# smart_well.net
KiCad netlist of a schematic drawn in EAGLE
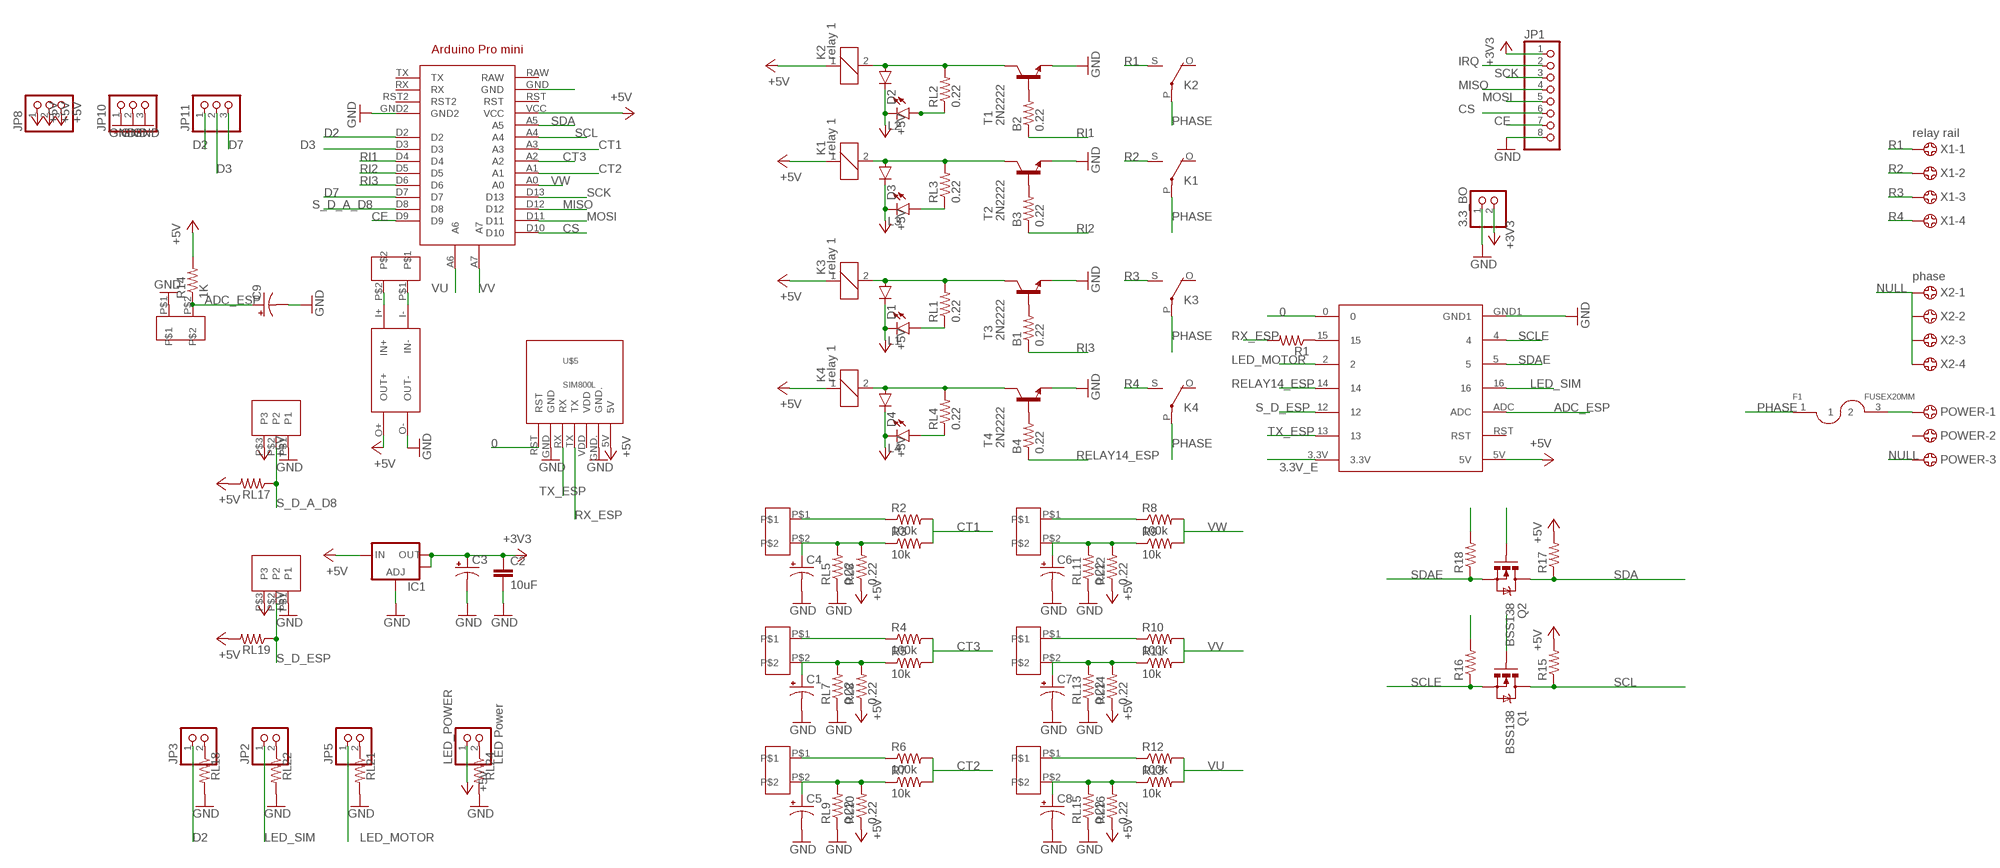
[diagram p0: schematic, sheet 1]

(export (version "E")
  (design (tool "Eeschema 10.0.6"))
  (components
    (comp (ref "3.3_BO")
      (value "PINHD-1X2")
      (footprint "eagle-import:1X02")
      (libsource (lib "eagle-import") (part "PINHD-1X2"))
    )
    (comp (ref "B1")
      (value "0.22")
      (footprint "eagle-import:0805")
      (libsource (lib "eagle-import") (part "0.22OHM-1/4W-1%(0805)"))
    )
    (comp (ref "B2")
      (value "0.22")
      (footprint "eagle-import:0805")
      (libsource (lib "eagle-import") (part "0.22OHM-1/4W-1%(0805)"))
    )
    (comp (ref "B3")
      (value "0.22")
      (footprint "eagle-import:0805")
      (libsource (lib "eagle-import") (part "0.22OHM-1/4W-1%(0805)"))
    )
    (comp (ref "B4")
      (value "0.22")
      (footprint "eagle-import:0805")
      (libsource (lib "eagle-import") (part "0.22OHM-1/4W-1%(0805)"))
    )
    (comp (ref "C1")
      (value "100UF-25V-20%(PTH)")
      (footprint "eagle-import:CPOL-RADIAL-100UF-25V")
      (libsource (lib "eagle-import") (part "100UF-25V-20%(PTH)"))
    )
    (comp (ref "C2")
      (value "10uF")
      (footprint "eagle-import:1210")
      (libsource (lib "eagle-import") (part "10UF50V20%(1210)"))
    )
    (comp (ref "C3")
      (value "100UF-25V-20%(PTH)")
      (footprint "eagle-import:CPOL-RADIAL-100UF-25V")
      (libsource (lib "eagle-import") (part "100UF-25V-20%(PTH)"))
    )
    (comp (ref "C4")
      (value "100UF-25V-20%(PTH)")
      (footprint "eagle-import:CPOL-RADIAL-100UF-25V")
      (libsource (lib "eagle-import") (part "100UF-25V-20%(PTH)"))
    )
    (comp (ref "C5")
      (value "100UF-25V-20%(PTH)")
      (footprint "eagle-import:CPOL-RADIAL-100UF-25V")
      (libsource (lib "eagle-import") (part "100UF-25V-20%(PTH)"))
    )
    (comp (ref "C6")
      (value "100UF-25V-20%(PTH)")
      (footprint "eagle-import:CPOL-RADIAL-100UF-25V")
      (libsource (lib "eagle-import") (part "100UF-25V-20%(PTH)"))
    )
    (comp (ref "C7")
      (value "100UF-25V-20%(PTH)")
      (footprint "eagle-import:CPOL-RADIAL-100UF-25V")
      (libsource (lib "eagle-import") (part "100UF-25V-20%(PTH)"))
    )
    (comp (ref "C8")
      (value "100UF-25V-20%(PTH)")
      (footprint "eagle-import:CPOL-RADIAL-100UF-25V")
      (libsource (lib "eagle-import") (part "100UF-25V-20%(PTH)"))
    )
    (comp (ref "C9")
      (value "10UF-25V-20%(PTH)KIT")
      (footprint "eagle-import:CPOL-RADIAL-10UF-25V-KIT")
      (libsource (lib "eagle-import") (part "10UF-25V-20%(PTH)KIT"))
    )
    (comp (ref "CT1")
      (value "ct1")
      (footprint "eagle-import:PIN_LOCK1X2")
      (libsource (lib "eagle-import") (part "PIN_LOCK_1X2"))
    )
    (comp (ref "CT2")
      (value "ct1")
      (footprint "eagle-import:PIN_LOCK1X2")
      (libsource (lib "eagle-import") (part "PIN_LOCK_1X2"))
    )
    (comp (ref "CT3")
      (value "ct1")
      (footprint "eagle-import:PIN_LOCK1X2")
      (libsource (lib "eagle-import") (part "PIN_LOCK_1X2"))
    )
    (comp (ref "CT4")
      (value "ct1")
      (footprint "eagle-import:PIN_LOCK1X2")
      (libsource (lib "eagle-import") (part "PIN_LOCK_1X2"))
    )
    (comp (ref "CT5")
      (value "ct1")
      (footprint "eagle-import:PIN_LOCK1X2")
      (libsource (lib "eagle-import") (part "PIN_LOCK_1X2"))
    )
    (comp (ref "CT6")
      (value "ct1")
      (footprint "eagle-import:PIN_LOCK1X2")
      (libsource (lib "eagle-import") (part "PIN_LOCK_1X2"))
    )
    (comp (ref "D1")
      (value "DIODEKIT2")
      (footprint "eagle-import:DIODE-1N4001-KIT")
      (libsource (lib "eagle-import") (part "DIODEKIT2"))
    )
    (comp (ref "D2")
      (value "DIODEKIT2")
      (footprint "eagle-import:DIODE-1N4001-KIT")
      (libsource (lib "eagle-import") (part "DIODEKIT2"))
    )
    (comp (ref "D3")
      (value "DIODEKIT2")
      (footprint "eagle-import:DIODE-1N4001-KIT")
      (libsource (lib "eagle-import") (part "DIODEKIT2"))
    )
    (comp (ref "D4")
      (value "DIODEKIT2")
      (footprint "eagle-import:DIODE-1N4001-KIT")
      (libsource (lib "eagle-import") (part "DIODEKIT2"))
    )
    (comp (ref "F1")
      (value "FUSEX20MM")
      (footprint "eagle-import:FUSE_5MM")
      (libsource (lib "eagle-import") (part "FUSEX20MM"))
    )
    (comp (ref "IC1")
      (value "V_REG_LM1117SOT223")
      (footprint "eagle-import:SOT223")
      (libsource (lib "eagle-import") (part "V_REG_LM1117SOT223"))
    )
    (comp (ref "JP1")
      (value "PINHD-1X8")
      (footprint "eagle-import:1X08")
      (libsource (lib "eagle-import") (part "PINHD-1X8"))
    )
    (comp (ref "JP2")
      (value "PINHD-1X2")
      (footprint "eagle-import:1X02")
      (libsource (lib "eagle-import") (part "PINHD-1X2"))
    )
    (comp (ref "JP3")
      (value "PINHD-1X2")
      (footprint "eagle-import:1X02")
      (libsource (lib "eagle-import") (part "PINHD-1X2"))
    )
    (comp (ref "JP5")
      (value "PINHD-1X2")
      (footprint "eagle-import:1X02")
      (libsource (lib "eagle-import") (part "PINHD-1X2"))
    )
    (comp (ref "JP8")
      (value "PINHD-1X3")
      (footprint "eagle-import:1X03")
      (libsource (lib "eagle-import") (part "PINHD-1X3"))
    )
    (comp (ref "JP10")
      (value "PINHD-1X3")
      (footprint "eagle-import:1X03")
      (libsource (lib "eagle-import") (part "PINHD-1X3"))
    )
    (comp (ref "JP11")
      (value "PINHD-1X3")
      (footprint "eagle-import:1X03")
      (libsource (lib "eagle-import") (part "PINHD-1X3"))
    )
    (comp (ref "K1")
      (value "relay 1")
      (footprint "eagle-import:G5LE")
      (libsource (lib "eagle-import") (part "G5LE"))
    )
    (comp (ref "K2")
      (value "relay 1")
      (footprint "eagle-import:G5LE")
      (libsource (lib "eagle-import") (part "G5LE"))
    )
    (comp (ref "K3")
      (value "relay 1")
      (footprint "eagle-import:G5LE")
      (libsource (lib "eagle-import") (part "G5LE"))
    )
    (comp (ref "K4")
      (value "relay 1")
      (footprint "eagle-import:G5LE")
      (libsource (lib "eagle-import") (part "G5LE"))
    )
    (comp (ref "L1")
      (value "LED3MM")
      (footprint "eagle-import:LED3MM")
      (libsource (lib "eagle-import") (part "LED3MM"))
    )
    (comp (ref "L2")
      (value "LED3MM")
      (footprint "eagle-import:LED3MM")
      (libsource (lib "eagle-import") (part "LED3MM"))
    )
    (comp (ref "L3")
      (value "LED3MM")
      (footprint "eagle-import:LED3MM")
      (libsource (lib "eagle-import") (part "LED3MM"))
    )
    (comp (ref "L4")
      (value "LED3MM")
      (footprint "eagle-import:LED3MM")
      (libsource (lib "eagle-import") (part "LED3MM"))
    )
    (comp (ref "LED_POWER")
      (value "LED Power")
      (footprint "eagle-import:1X02")
      (libsource (lib "eagle-import") (part "PINHD-1X2"))
    )
    (comp (ref "POWER")
      (value "5202-03-N-02")
      (footprint "eagle-import:5202-03-N-02")
      (libsource (lib "eagle-import") (part "5202-03-N-02"))
    )
    (comp (ref "Q1")
      (value "BSS138")
      (footprint "eagle-import:SOT23-3")
      (libsource (lib "eagle-import") (part "MOSFET-NCHANNELBSS138"))
    )
    (comp (ref "Q2")
      (value "BSS138")
      (footprint "eagle-import:SOT23-3")
      (libsource (lib "eagle-import") (part "MOSFET-NCHANNELBSS138"))
    )
    (comp (ref "R1")
      (value "0.3OHM-1/8W-1%(0805)")
      (footprint "eagle-import:0805")
      (libsource (lib "eagle-import") (part "0.3OHM-1/8W-1%(0805)"))
    )
    (comp (ref "R2")
      (value "100k")
      (footprint "eagle-import:AXIAL-0.1")
      (libsource (lib "eagle-import") (part "10OHM-1/4W-5%(PTH)VERT"))
    )
    (comp (ref "R3")
      (value "10k")
      (footprint "eagle-import:AXIAL-0.1")
      (libsource (lib "eagle-import") (part "10OHM-1/4W-5%(PTH)VERT"))
    )
    (comp (ref "R4")
      (value "100k")
      (footprint "eagle-import:AXIAL-0.1")
      (libsource (lib "eagle-import") (part "10OHM-1/4W-5%(PTH)VERT"))
    )
    (comp (ref "R5")
      (value "10k")
      (footprint "eagle-import:AXIAL-0.1")
      (libsource (lib "eagle-import") (part "10OHM-1/4W-5%(PTH)VERT"))
    )
    (comp (ref "R6")
      (value "100k")
      (footprint "eagle-import:AXIAL-0.1")
      (libsource (lib "eagle-import") (part "10OHM-1/4W-5%(PTH)VERT"))
    )
    (comp (ref "R7")
      (value "10k")
      (footprint "eagle-import:AXIAL-0.1")
      (libsource (lib "eagle-import") (part "10OHM-1/4W-5%(PTH)VERT"))
    )
    (comp (ref "R8")
      (value "100k")
      (footprint "eagle-import:AXIAL-0.1")
      (libsource (lib "eagle-import") (part "10OHM-1/4W-5%(PTH)VERT"))
    )
    (comp (ref "R9")
      (value "10k")
      (footprint "eagle-import:AXIAL-0.1")
      (libsource (lib "eagle-import") (part "10OHM-1/4W-5%(PTH)VERT"))
    )
    (comp (ref "R10")
      (value "100k")
      (footprint "eagle-import:AXIAL-0.1")
      (libsource (lib "eagle-import") (part "10OHM-1/4W-5%(PTH)VERT"))
    )
    (comp (ref "R11")
      (value "10k")
      (footprint "eagle-import:AXIAL-0.1")
      (libsource (lib "eagle-import") (part "10OHM-1/4W-5%(PTH)VERT"))
    )
    (comp (ref "R12")
      (value "100k")
      (footprint "eagle-import:AXIAL-0.1")
      (libsource (lib "eagle-import") (part "10OHM-1/4W-5%(PTH)VERT"))
    )
    (comp (ref "R13")
      (value "10k")
      (footprint "eagle-import:AXIAL-0.1")
      (libsource (lib "eagle-import") (part "10OHM-1/4W-5%(PTH)VERT"))
    )
    (comp (ref "R14")
      (value "1K")
      (footprint "eagle-import:AXIAL-0.1")
      (libsource (lib "eagle-import") (part "1KOHM-1/4W-1%(PTH)VERT"))
    )
    (comp (ref "R15")
      (value "0.22OHM-1/4W-1%(0805)")
      (footprint "eagle-import:0805")
      (libsource (lib "eagle-import") (part "0.22OHM-1/4W-1%(0805)"))
    )
    (comp (ref "R16")
      (value "0.22OHM-1/4W-1%(0805)")
      (footprint "eagle-import:0805")
      (libsource (lib "eagle-import") (part "0.22OHM-1/4W-1%(0805)"))
    )
    (comp (ref "R17")
      (value "0.22OHM-1/4W-1%(0805)")
      (footprint "eagle-import:0805")
      (libsource (lib "eagle-import") (part "0.22OHM-1/4W-1%(0805)"))
    )
    (comp (ref "R18")
      (value "0.22OHM-1/4W-1%(0805)")
      (footprint "eagle-import:0805")
      (libsource (lib "eagle-import") (part "0.22OHM-1/4W-1%(0805)"))
    )
    (comp (ref "RL1")
      (value "0.22")
      (footprint "eagle-import:0805")
      (libsource (lib "eagle-import") (part "0.22OHM-1/4W-1%(0805)"))
    )
    (comp (ref "RL2")
      (value "0.22")
      (footprint "eagle-import:0805")
      (libsource (lib "eagle-import") (part "0.22OHM-1/4W-1%(0805)"))
    )
    (comp (ref "RL3")
      (value "0.22")
      (footprint "eagle-import:0805")
      (libsource (lib "eagle-import") (part "0.22OHM-1/4W-1%(0805)"))
    )
    (comp (ref "RL4")
      (value "0.22")
      (footprint "eagle-import:0805")
      (libsource (lib "eagle-import") (part "0.22OHM-1/4W-1%(0805)"))
    )
    (comp (ref "RL5")
      (value "0.22")
      (footprint "eagle-import:0805")
      (libsource (lib "eagle-import") (part "0.22OHM-1/4W-1%(0805)"))
    )
    (comp (ref "RL6")
      (value "0.22")
      (footprint "eagle-import:0805")
      (libsource (lib "eagle-import") (part "0.22OHM-1/4W-1%(0805)"))
    )
    (comp (ref "RL7")
      (value "0.22")
      (footprint "eagle-import:0805")
      (libsource (lib "eagle-import") (part "0.22OHM-1/4W-1%(0805)"))
    )
    (comp (ref "RL8")
      (value "0.22")
      (footprint "eagle-import:0805")
      (libsource (lib "eagle-import") (part "0.22OHM-1/4W-1%(0805)"))
    )
    (comp (ref "RL9")
      (value "0.22")
      (footprint "eagle-import:0805")
      (libsource (lib "eagle-import") (part "0.22OHM-1/4W-1%(0805)"))
    )
    (comp (ref "RL10")
      (value "0.22")
      (footprint "eagle-import:0805")
      (libsource (lib "eagle-import") (part "0.22OHM-1/4W-1%(0805)"))
    )
    (comp (ref "RL11")
      (value "0.22")
      (footprint "eagle-import:0805")
      (libsource (lib "eagle-import") (part "0.22OHM-1/4W-1%(0805)"))
    )
    (comp (ref "RL12")
      (value "0.22")
      (footprint "eagle-import:0805")
      (libsource (lib "eagle-import") (part "0.22OHM-1/4W-1%(0805)"))
    )
    (comp (ref "RL13")
      (value "0.22")
      (footprint "eagle-import:0805")
      (libsource (lib "eagle-import") (part "0.22OHM-1/4W-1%(0805)"))
    )
    (comp (ref "RL14")
      (value "0.22")
      (footprint "eagle-import:0805")
      (libsource (lib "eagle-import") (part "0.22OHM-1/4W-1%(0805)"))
    )
    (comp (ref "RL15")
      (value "0.22")
      (footprint "eagle-import:0805")
      (libsource (lib "eagle-import") (part "0.22OHM-1/4W-1%(0805)"))
    )
    (comp (ref "RL16")
      (value "0.22")
      (footprint "eagle-import:0805")
      (libsource (lib "eagle-import") (part "0.22OHM-1/4W-1%(0805)"))
    )
    (comp (ref "RL17")
      (value "0.22OHM-1/4W-1%(0805)")
      (footprint "eagle-import:0805")
      (libsource (lib "eagle-import") (part "0.22OHM-1/4W-1%(0805)"))
    )
    (comp (ref "RL18")
      (value "0.22OHM-1/4W-1%(0805)")
      (footprint "eagle-import:0805")
      (libsource (lib "eagle-import") (part "0.22OHM-1/4W-1%(0805)"))
    )
    (comp (ref "RL19")
      (value "0.22OHM-1/4W-1%(0805)")
      (footprint "eagle-import:0805")
      (libsource (lib "eagle-import") (part "0.22OHM-1/4W-1%(0805)"))
    )
    (comp (ref "RL21")
      (value "0.22OHM-1/4W-1%(0805)")
      (footprint "eagle-import:0805")
      (libsource (lib "eagle-import") (part "0.22OHM-1/4W-1%(0805)"))
    )
    (comp (ref "RL22")
      (value "0.22OHM-1/4W-1%(0805)")
      (footprint "eagle-import:0805")
      (libsource (lib "eagle-import") (part "0.22OHM-1/4W-1%(0805)"))
    )
    (comp (ref "RL24")
      (value "0.22OHM-1/4W-1%(0805)")
      (footprint "eagle-import:0805")
      (libsource (lib "eagle-import") (part "0.22OHM-1/4W-1%(0805)"))
    )
    (comp (ref "T1")
      (value "2N2222")
      (footprint "eagle-import:TO92-EBC-OVAL")
      (libsource (lib "eagle-import") (part "2N2222"))
    )
    (comp (ref "T2")
      (value "2N2222")
      (footprint "eagle-import:TO92-EBC-OVAL")
      (libsource (lib "eagle-import") (part "2N2222"))
    )
    (comp (ref "T3")
      (value "2N2222")
      (footprint "eagle-import:TO92-EBC-OVAL")
      (libsource (lib "eagle-import") (part "2N2222"))
    )
    (comp (ref "T4")
      (value "2N2222")
      (footprint "eagle-import:TO92-EBC-OVAL")
      (libsource (lib "eagle-import") (part "2N2222"))
    )
    (comp (ref "U$2")
      (value "PIN_LOCK_1X3")
      (footprint "eagle-import:PIN_LOCK1X3")
      (libsource (lib "eagle-import") (part "PIN_LOCK_1X3"))
    )
    (comp (ref "U$3")
      (value "ESP12F_SHEILD10PIN")
      (footprint "eagle-import:ESP12F_SHEILD10PIN")
      (libsource (lib "eagle-import") (part "ESP12F_SHEILD10PIN"))
    )
    (comp (ref "U$5")
      (value "SIM800L")
      (footprint "eagle-import:SIM800L")
      (libsource (lib "eagle-import") (part "SIM800L"))
    )
    (comp (ref "U$6")
      (value "DC-DC")
      (footprint "eagle-import:DC-DC")
      (libsource (lib "eagle-import") (part "DC-DC"))
    )
    (comp (ref "U$7")
      (value "ARDUINO_DIP")
      (footprint "eagle-import:ARDUINO_DIP")
      (libsource (lib "eagle-import") (part "ARDUINO_DIP"))
    )
    (comp (ref "U$8")
      (value "PIN_LOCK_1X3")
      (footprint "eagle-import:PIN_LOCK1X3")
      (libsource (lib "eagle-import") (part "PIN_LOCK_1X3"))
    )
    (comp (ref "U$9")
      (value "PIN_LOCK_1X2")
      (footprint "eagle-import:PIN_LOCK1X2")
      (libsource (lib "eagle-import") (part "PIN_LOCK_1X2"))
    )
    (comp (ref "U$11")
      (value "PIN_LOCK_1X2")
      (footprint "eagle-import:PIN_LOCK1X2")
      (libsource (lib "eagle-import") (part "PIN_LOCK_1X2"))
    )
    (comp (ref "X1")
      (value "relay rail")
      (footprint "eagle-import:5202-04-N-02")
      (libsource (lib "eagle-import") (part "5202-04-N-02"))
    )
    (comp (ref "X2")
      (value "phase")
      (footprint "eagle-import:5202-04-N-02")
      (libsource (lib "eagle-import") (part "5202-04-N-02"))
    )
  )
  (nets
    (net (code "1") (name "+3V3") (class "Default")
      (node (ref "3.3_BO") (pin "2") (pinfunction "2_2") (pintype "passive"))
      (node (ref "C2") (pin "1") (pinfunction "1_1") (pintype "passive"))
      (node (ref "C3") (pin "1") (pinfunction "+_1") (pintype "passive"))
      (node (ref "IC1") (pin "2") (pinfunction "OUT_2") (pintype "output"))
      (node (ref "IC1") (pin "4") (pinfunction "OUT_4") (pintype "output"))
      (node (ref "JP1") (pin "1") (pinfunction "1_1") (pintype "passive"))
    )
    (net (code "2") (name "+5V") (class "Default")
      (node (ref "D1") (pin "C") (pinfunction "C_C") (pintype "passive"))
      (node (ref "D2") (pin "C") (pinfunction "C_C") (pintype "passive"))
      (node (ref "D3") (pin "C") (pinfunction "C_C") (pintype "passive"))
      (node (ref "D4") (pin "C") (pinfunction "C_C") (pintype "passive"))
      (node (ref "IC1") (pin "3") (pinfunction "IN_3") (pintype "input"))
      (node (ref "JP8") (pin "1") (pinfunction "1_1") (pintype "passive"))
      (node (ref "JP8") (pin "2") (pinfunction "2_2") (pintype "passive"))
      (node (ref "JP8") (pin "3") (pinfunction "3_3") (pintype "passive"))
      (node (ref "K1") (pin "1") (pinfunction "1_1") (pintype "passive"))
      (node (ref "K2") (pin "1") (pinfunction "1_1") (pintype "passive"))
      (node (ref "K3") (pin "1") (pinfunction "1_1") (pintype "passive"))
      (node (ref "K4") (pin "1") (pinfunction "1_1") (pintype "passive"))
      (node (ref "L1") (pin "K") (pinfunction "C_K") (pintype "passive"))
      (node (ref "L2") (pin "K") (pinfunction "C_K") (pintype "passive"))
      (node (ref "L3") (pin "K") (pinfunction "C_K") (pintype "passive"))
      (node (ref "L4") (pin "K") (pinfunction "C_K") (pintype "passive"))
      (node (ref "LED_POWER") (pin "1") (pinfunction "1_1") (pintype "passive"))
      (node (ref "R14") (pin "P$2") (pinfunction "2_P$2") (pintype "passive"))
      (node (ref "R15") (pin "2") (pinfunction "2_2") (pintype "passive"))
      (node (ref "R17") (pin "2") (pinfunction "2_2") (pintype "passive"))
      (node (ref "RL10") (pin "1") (pinfunction "1_1") (pintype "passive"))
      (node (ref "RL12") (pin "1") (pinfunction "1_1") (pintype "passive"))
      (node (ref "RL14") (pin "1") (pinfunction "1_1") (pintype "passive"))
      (node (ref "RL16") (pin "1") (pinfunction "1_1") (pintype "passive"))
      (node (ref "RL17") (pin "2") (pinfunction "2_2") (pintype "passive"))
      (node (ref "RL19") (pin "2") (pinfunction "2_2") (pintype "passive"))
      (node (ref "RL6") (pin "1") (pinfunction "1_1") (pintype "passive"))
      (node (ref "RL8") (pin "1") (pinfunction "1_1") (pintype "passive"))
      (node (ref "U$2") (pin "P$3") (pinfunction "P3_P$3") (pintype "bidirectional"))
      (node (ref "U$3") (pin "5V") (pinfunction "5V_5V") (pintype "bidirectional"))
      (node (ref "U$5") (pin "5V") (pinfunction "5V_5V") (pintype "bidirectional"))
      (node (ref "U$6") (pin "O+") (pinfunction "OUT+_O+") (pintype "bidirectional"))
      (node (ref "U$7") (pin "VCC") (pinfunction "VCC_VCC") (pintype "power_in"))
      (node (ref "U$8") (pin "P$3") (pinfunction "P3_P$3") (pintype "bidirectional"))
    )
    (net (code "3") (name "/0") (class "Default")
      (node (ref "U$3") (pin "0") (pinfunction "0_0") (pintype "bidirectional"))
      (node (ref "U$5") (pin "RST") (pinfunction "RST_RST") (pintype "bidirectional"))
    )
    (net (code "4") (name "/3.3V_E") (class "Default")
      (node (ref "Q1") (pin "1") (pinfunction "G_1") (pintype "passive"))
      (node (ref "Q2") (pin "1") (pinfunction "G_1") (pintype "passive"))
      (node (ref "R16") (pin "2") (pinfunction "2_2") (pintype "passive"))
      (node (ref "R18") (pin "2") (pinfunction "2_2") (pintype "passive"))
      (node (ref "U$3") (pin "3.3V") (pinfunction "3.3V_3.3V") (pintype "bidirectional"))
    )
    (net (code "5") (name "/ADC_ESP") (class "Default")
      (node (ref "C9") (pin "1") (pinfunction "+_1") (pintype "passive"))
      (node (ref "R14") (pin "P$1") (pinfunction "1_P$1") (pintype "passive"))
      (node (ref "U$11") (pin "P$2") (pinfunction "P$2_P$2") (pintype "bidirectional"))
      (node (ref "U$3") (pin "ADC") (pinfunction "ADC_ADC") (pintype "bidirectional"))
    )
    (net (code "6") (name "/CE") (class "Default")
      (node (ref "JP1") (pin "7") (pinfunction "7_7") (pintype "passive"))
      (node (ref "U$7") (pin "D9") (pinfunction "D9_D9") (pintype "bidirectional"))
    )
    (net (code "7") (name "/CS") (class "Default")
      (node (ref "JP1") (pin "6") (pinfunction "6_6") (pintype "passive"))
      (node (ref "U$7") (pin "D10") (pinfunction "D10_D10") (pintype "bidirectional"))
    )
    (net (code "8") (name "/CT1") (class "Default")
      (node (ref "R2") (pin "P$2") (pinfunction "2_P$2") (pintype "passive"))
      (node (ref "R3") (pin "P$2") (pinfunction "2_P$2") (pintype "passive"))
      (node (ref "U$7") (pin "A3") (pinfunction "A3_A3") (pintype "bidirectional"))
    )
    (net (code "9") (name "/CT2") (class "Default")
      (node (ref "R6") (pin "P$2") (pinfunction "2_P$2") (pintype "passive"))
      (node (ref "R7") (pin "P$2") (pinfunction "2_P$2") (pintype "passive"))
      (node (ref "U$7") (pin "A1") (pinfunction "A1_A1") (pintype "bidirectional"))
    )
    (net (code "10") (name "/CT3") (class "Default")
      (node (ref "R4") (pin "P$2") (pinfunction "2_P$2") (pintype "passive"))
      (node (ref "R5") (pin "P$2") (pinfunction "2_P$2") (pintype "passive"))
      (node (ref "U$7") (pin "A2") (pinfunction "A2_A2") (pintype "bidirectional"))
    )
    (net (code "11") (name "/D2") (class "Default")
      (node (ref "JP11") (pin "1") (pinfunction "1_1") (pintype "passive"))
      (node (ref "JP3") (pin "1") (pinfunction "1_1") (pintype "passive"))
      (node (ref "U$7") (pin "D2") (pinfunction "D2_D2") (pintype "bidirectional"))
    )
    (net (code "12") (name "/D3") (class "Default")
      (node (ref "JP11") (pin "2") (pinfunction "2_2") (pintype "passive"))
      (node (ref "U$7") (pin "D3") (pinfunction "D3_D3") (pintype "bidirectional"))
    )
    (net (code "13") (name "/D7") (class "Default")
      (node (ref "JP11") (pin "3") (pinfunction "3_3") (pintype "passive"))
      (node (ref "U$7") (pin "D7") (pinfunction "D7_D7") (pintype "bidirectional"))
    )
    (net (code "14") (name "/IRQ") (class "Default")
      (node (ref "JP1") (pin "2") (pinfunction "2_2") (pintype "passive"))
    )
    (net (code "15") (name "/LED_MOTOR") (class "Default")
      (node (ref "JP5") (pin "1") (pinfunction "1_1") (pintype "passive"))
      (node (ref "U$3") (pin "2") (pinfunction "2_2") (pintype "bidirectional"))
    )
    (net (code "16") (name "/LED_SIM") (class "Default")
      (node (ref "JP2") (pin "1") (pinfunction "1_1") (pintype "passive"))
      (node (ref "U$3") (pin "16") (pinfunction "16_16") (pintype "bidirectional"))
    )
    (net (code "17") (name "/MISO") (class "Default")
      (node (ref "JP1") (pin "4") (pinfunction "4_4") (pintype "passive"))
      (node (ref "U$7") (pin "D12") (pinfunction "D12_D12") (pintype "bidirectional"))
    )
    (net (code "18") (name "/MOSI") (class "Default")
      (node (ref "JP1") (pin "5") (pinfunction "5_5") (pintype "passive"))
      (node (ref "U$7") (pin "D11") (pinfunction "D11_D11") (pintype "bidirectional"))
    )
    (net (code "19") (name "/NULL") (class "Default")
      (node (ref "POWER") (pin "3") (pinfunction "1_3") (pintype "passive"))
      (node (ref "X2") (pin "1") (pinfunction "1_1") (pintype "passive"))
      (node (ref "X2") (pin "2") (pinfunction "1_2") (pintype "passive"))
      (node (ref "X2") (pin "3") (pinfunction "1_3") (pintype "passive"))
      (node (ref "X2") (pin "4") (pinfunction "1_4") (pintype "passive"))
    )
    (net (code "20") (name "/PHASE") (class "Default")
      (node (ref "F1") (pin "1") (pinfunction "1_1") (pintype "bidirectional"))
      (node (ref "K1") (pin "P") (pinfunction "P_P") (pintype "passive"))
      (node (ref "K2") (pin "P") (pinfunction "P_P") (pintype "passive"))
      (node (ref "K3") (pin "P") (pinfunction "P_P") (pintype "passive"))
      (node (ref "K4") (pin "P") (pinfunction "P_P") (pintype "passive"))
    )
    (net (code "21") (name "/R1") (class "Default")
      (node (ref "K2") (pin "S") (pinfunction "S_S") (pintype "passive"))
      (node (ref "X1") (pin "1") (pinfunction "1_1") (pintype "passive"))
    )
    (net (code "22") (name "/R2") (class "Default")
      (node (ref "K1") (pin "S") (pinfunction "S_S") (pintype "passive"))
      (node (ref "X1") (pin "2") (pinfunction "1_2") (pintype "passive"))
    )
    (net (code "23") (name "/R3") (class "Default")
      (node (ref "K3") (pin "S") (pinfunction "S_S") (pintype "passive"))
      (node (ref "X1") (pin "3") (pinfunction "1_3") (pintype "passive"))
    )
    (net (code "24") (name "/R4") (class "Default")
      (node (ref "K4") (pin "S") (pinfunction "S_S") (pintype "passive"))
      (node (ref "X1") (pin "4") (pinfunction "1_4") (pintype "passive"))
    )
    (net (code "25") (name "/RELAY14_ESP") (class "Default")
      (node (ref "B4") (pin "1") (pinfunction "1_1") (pintype "passive"))
      (node (ref "U$3") (pin "14") (pinfunction "14_14") (pintype "bidirectional"))
    )
    (net (code "26") (name "/RI1") (class "Default")
      (node (ref "B2") (pin "1") (pinfunction "1_1") (pintype "passive"))
      (node (ref "U$7") (pin "D4") (pinfunction "D4_D4") (pintype "bidirectional"))
    )
    (net (code "27") (name "/RI2") (class "Default")
      (node (ref "B3") (pin "1") (pinfunction "1_1") (pintype "passive"))
      (node (ref "U$7") (pin "D5") (pinfunction "D5_D5") (pintype "bidirectional"))
    )
    (net (code "28") (name "/RI3") (class "Default")
      (node (ref "B1") (pin "1") (pinfunction "1_1") (pintype "passive"))
      (node (ref "U$7") (pin "D6") (pinfunction "D6_D6") (pintype "bidirectional"))
    )
    (net (code "29") (name "/RX_ESP") (class "Default")
      (node (ref "R1") (pin "2") (pinfunction "2_2") (pintype "passive"))
      (node (ref "U$5") (pin "TX") (pinfunction "TX_TX") (pintype "bidirectional"))
    )
    (net (code "30") (name "/SCK") (class "Default")
      (node (ref "JP1") (pin "3") (pinfunction "3_3") (pintype "passive"))
      (node (ref "U$7") (pin "D13") (pinfunction "D13_D13") (pintype "bidirectional"))
    )
    (net (code "31") (name "/SCL") (class "Default")
      (node (ref "Q1") (pin "3") (pinfunction "D_3") (pintype "passive"))
      (node (ref "R15") (pin "1") (pinfunction "1_1") (pintype "passive"))
      (node (ref "U$7") (pin "A4") (pinfunction "A4_A4") (pintype "bidirectional"))
    )
    (net (code "32") (name "/SCLE") (class "Default")
      (node (ref "Q1") (pin "2") (pinfunction "S_2") (pintype "passive"))
      (node (ref "R16") (pin "1") (pinfunction "1_1") (pintype "passive"))
      (node (ref "U$3") (pin "4") (pinfunction "4_4") (pintype "bidirectional"))
    )
    (net (code "33") (name "/SDA") (class "Default")
      (node (ref "Q2") (pin "3") (pinfunction "D_3") (pintype "passive"))
      (node (ref "R17") (pin "1") (pinfunction "1_1") (pintype "passive"))
      (node (ref "U$7") (pin "A5") (pinfunction "A5_A5") (pintype "bidirectional"))
    )
    (net (code "34") (name "/SDAE") (class "Default")
      (node (ref "Q2") (pin "2") (pinfunction "S_2") (pintype "passive"))
      (node (ref "R18") (pin "1") (pinfunction "1_1") (pintype "passive"))
      (node (ref "U$3") (pin "5") (pinfunction "5_5") (pintype "bidirectional"))
    )
    (net (code "35") (name "/S_D_A_D8") (class "Default")
      (node (ref "RL17") (pin "1") (pinfunction "1_1") (pintype "passive"))
      (node (ref "U$2") (pin "P$2") (pinfunction "P2_P$2") (pintype "bidirectional"))
      (node (ref "U$7") (pin "D8") (pinfunction "D8_D8") (pintype "bidirectional"))
    )
    (net (code "36") (name "/S_D_ESP") (class "Default")
      (node (ref "RL19") (pin "1") (pinfunction "1_1") (pintype "passive"))
      (node (ref "U$3") (pin "12") (pinfunction "12_12") (pintype "bidirectional"))
      (node (ref "U$8") (pin "P$2") (pinfunction "P2_P$2") (pintype "bidirectional"))
    )
    (net (code "37") (name "/TX_ESP") (class "Default")
      (node (ref "U$3") (pin "13") (pinfunction "13_13") (pintype "bidirectional"))
      (node (ref "U$5") (pin "RX") (pinfunction "RX_RX") (pintype "bidirectional"))
    )
    (net (code "38") (name "/VU") (class "Default")
      (node (ref "R12") (pin "P$2") (pinfunction "2_P$2") (pintype "passive"))
      (node (ref "R13") (pin "P$2") (pinfunction "2_P$2") (pintype "passive"))
      (node (ref "U$7") (pin "A6") (pinfunction "A6_A6") (pintype "bidirectional"))
    )
    (net (code "39") (name "/VV") (class "Default")
      (node (ref "R10") (pin "P$2") (pinfunction "2_P$2") (pintype "passive"))
      (node (ref "R11") (pin "P$2") (pinfunction "2_P$2") (pintype "passive"))
      (node (ref "U$7") (pin "A7") (pinfunction "A7_A7") (pintype "bidirectional"))
    )
    (net (code "40") (name "/VW") (class "Default")
      (node (ref "R8") (pin "P$2") (pinfunction "2_P$2") (pintype "passive"))
      (node (ref "R9") (pin "P$2") (pinfunction "2_P$2") (pintype "passive"))
      (node (ref "U$7") (pin "A0") (pinfunction "A0_A0") (pintype "bidirectional"))
    )
    (net (code "41") (name "GND") (class "Default")
      (node (ref "3.3_BO") (pin "1") (pinfunction "1_1") (pintype "passive"))
      (node (ref "C1") (pin "2") (pinfunction "-_2") (pintype "passive"))
      (node (ref "C2") (pin "2") (pinfunction "2_2") (pintype "passive"))
      (node (ref "C3") (pin "2") (pinfunction "-_2") (pintype "passive"))
      (node (ref "C4") (pin "2") (pinfunction "-_2") (pintype "passive"))
      (node (ref "C5") (pin "2") (pinfunction "-_2") (pintype "passive"))
      (node (ref "C6") (pin "2") (pinfunction "-_2") (pintype "passive"))
      (node (ref "C7") (pin "2") (pinfunction "-_2") (pintype "passive"))
      (node (ref "C8") (pin "2") (pinfunction "-_2") (pintype "passive"))
      (node (ref "C9") (pin "2") (pinfunction "-_2") (pintype "passive"))
      (node (ref "IC1") (pin "1") (pinfunction "ADJ_1") (pintype "input"))
      (node (ref "JP1") (pin "8") (pinfunction "8_8") (pintype "passive"))
      (node (ref "JP10") (pin "1") (pinfunction "1_1") (pintype "passive"))
      (node (ref "JP10") (pin "2") (pinfunction "2_2") (pintype "passive"))
      (node (ref "JP10") (pin "3") (pinfunction "3_3") (pintype "passive"))
      (node (ref "RL11") (pin "1") (pinfunction "1_1") (pintype "passive"))
      (node (ref "RL13") (pin "1") (pinfunction "1_1") (pintype "passive"))
      (node (ref "RL15") (pin "1") (pinfunction "1_1") (pintype "passive"))
      (node (ref "RL18") (pin "2") (pinfunction "2_2") (pintype "passive"))
      (node (ref "RL21") (pin "2") (pinfunction "2_2") (pintype "passive"))
      (node (ref "RL22") (pin "2") (pinfunction "2_2") (pintype "passive"))
      (node (ref "RL24") (pin "2") (pinfunction "2_2") (pintype "passive"))
      (node (ref "RL5") (pin "1") (pinfunction "1_1") (pintype "passive"))
      (node (ref "RL7") (pin "1") (pinfunction "1_1") (pintype "passive"))
      (node (ref "RL9") (pin "1") (pinfunction "1_1") (pintype "passive"))
      (node (ref "T1") (pin "E") (pinfunction "E_E") (pintype "passive"))
      (node (ref "T2") (pin "E") (pinfunction "E_E") (pintype "passive"))
      (node (ref "T3") (pin "E") (pinfunction "E_E") (pintype "passive"))
      (node (ref "T4") (pin "E") (pinfunction "E_E") (pintype "passive"))
      (node (ref "U$11") (pin "P$1") (pinfunction "P$1_P$1") (pintype "bidirectional"))
      (node (ref "U$2") (pin "P$1") (pinfunction "P1_P$1") (pintype "bidirectional"))
      (node (ref "U$3") (pin "GND1") (pinfunction "GND1_GND1") (pintype "bidirectional"))
      (node (ref "U$5") (pin "GND") (pinfunction "GND_GND") (pintype "bidirectional"))
      (node (ref "U$5") (pin "GND.") (pinfunction "GND._GND.") (pintype "bidirectional"))
      (node (ref "U$6") (pin "O-") (pinfunction "OUT-_O-") (pintype "bidirectional"))
      (node (ref "U$7") (pin "GND2") (pinfunction "GND2_GND2") (pintype "bidirectional"))
      (node (ref "U$8") (pin "P$1") (pinfunction "P1_P$1") (pintype "bidirectional"))
    )
    (net (code "42") (name "Net-(B1-Pad2)") (class "Default")
      (node (ref "B1") (pin "2") (pinfunction "2_2") (pintype "passive"))
      (node (ref "T3") (pin "B") (pinfunction "B_B") (pintype "passive"))
    )
    (net (code "43") (name "Net-(B2-Pad2)") (class "Default")
      (node (ref "B2") (pin "2") (pinfunction "2_2") (pintype "passive"))
      (node (ref "T1") (pin "B") (pinfunction "B_B") (pintype "passive"))
    )
    (net (code "44") (name "Net-(B3-Pad2)") (class "Default")
      (node (ref "B3") (pin "2") (pinfunction "2_2") (pintype "passive"))
      (node (ref "T2") (pin "B") (pinfunction "B_B") (pintype "passive"))
    )
    (net (code "45") (name "Net-(B4-Pad2)") (class "Default")
      (node (ref "B4") (pin "2") (pinfunction "2_2") (pintype "passive"))
      (node (ref "T4") (pin "B") (pinfunction "B_B") (pintype "passive"))
    )
    (net (code "46") (name "Net-(C1-+)") (class "Default")
      (node (ref "C1") (pin "1") (pinfunction "+_1") (pintype "passive"))
      (node (ref "CT2") (pin "P$2") (pinfunction "P$2_P$2") (pintype "bidirectional"))
      (node (ref "R5") (pin "P$1") (pinfunction "1_P$1") (pintype "passive"))
      (node (ref "RL7") (pin "2") (pinfunction "2_2") (pintype "passive"))
      (node (ref "RL8") (pin "2") (pinfunction "2_2") (pintype "passive"))
    )
    (net (code "47") (name "Net-(C4-+)") (class "Default")
      (node (ref "C4") (pin "1") (pinfunction "+_1") (pintype "passive"))
      (node (ref "CT1") (pin "P$2") (pinfunction "P$2_P$2") (pintype "bidirectional"))
      (node (ref "R3") (pin "P$1") (pinfunction "1_P$1") (pintype "passive"))
      (node (ref "RL5") (pin "2") (pinfunction "2_2") (pintype "passive"))
      (node (ref "RL6") (pin "2") (pinfunction "2_2") (pintype "passive"))
    )
    (net (code "48") (name "Net-(C5-+)") (class "Default")
      (node (ref "C5") (pin "1") (pinfunction "+_1") (pintype "passive"))
      (node (ref "CT3") (pin "P$2") (pinfunction "P$2_P$2") (pintype "bidirectional"))
      (node (ref "R7") (pin "P$1") (pinfunction "1_P$1") (pintype "passive"))
      (node (ref "RL10") (pin "2") (pinfunction "2_2") (pintype "passive"))
      (node (ref "RL9") (pin "2") (pinfunction "2_2") (pintype "passive"))
    )
    (net (code "49") (name "Net-(C6-+)") (class "Default")
      (node (ref "C6") (pin "1") (pinfunction "+_1") (pintype "passive"))
      (node (ref "CT4") (pin "P$2") (pinfunction "P$2_P$2") (pintype "bidirectional"))
      (node (ref "R9") (pin "P$1") (pinfunction "1_P$1") (pintype "passive"))
      (node (ref "RL11") (pin "2") (pinfunction "2_2") (pintype "passive"))
      (node (ref "RL12") (pin "2") (pinfunction "2_2") (pintype "passive"))
    )
    (net (code "50") (name "Net-(C7-+)") (class "Default")
      (node (ref "C7") (pin "1") (pinfunction "+_1") (pintype "passive"))
      (node (ref "CT5") (pin "P$2") (pinfunction "P$2_P$2") (pintype "bidirectional"))
      (node (ref "R11") (pin "P$1") (pinfunction "1_P$1") (pintype "passive"))
      (node (ref "RL13") (pin "2") (pinfunction "2_2") (pintype "passive"))
      (node (ref "RL14") (pin "2") (pinfunction "2_2") (pintype "passive"))
    )
    (net (code "51") (name "Net-(C8-+)") (class "Default")
      (node (ref "C8") (pin "1") (pinfunction "+_1") (pintype "passive"))
      (node (ref "CT6") (pin "P$2") (pinfunction "P$2_P$2") (pintype "bidirectional"))
      (node (ref "R13") (pin "P$1") (pinfunction "1_P$1") (pintype "passive"))
      (node (ref "RL15") (pin "2") (pinfunction "2_2") (pintype "passive"))
      (node (ref "RL16") (pin "2") (pinfunction "2_2") (pintype "passive"))
    )
    (net (code "52") (name "Net-(D1-PadA)") (class "Default")
      (node (ref "D1") (pin "A") (pinfunction "A_A") (pintype "passive"))
      (node (ref "K3") (pin "2") (pinfunction "2_2") (pintype "passive"))
      (node (ref "RL1") (pin "2") (pinfunction "2_2") (pintype "passive"))
      (node (ref "T3") (pin "C") (pinfunction "C_C") (pintype "passive"))
    )
    (net (code "53") (name "Net-(D2-PadA)") (class "Default")
      (node (ref "D2") (pin "A") (pinfunction "A_A") (pintype "passive"))
      (node (ref "K2") (pin "2") (pinfunction "2_2") (pintype "passive"))
      (node (ref "RL2") (pin "2") (pinfunction "2_2") (pintype "passive"))
      (node (ref "T1") (pin "C") (pinfunction "C_C") (pintype "passive"))
    )
    (net (code "54") (name "Net-(D3-PadA)") (class "Default")
      (node (ref "D3") (pin "A") (pinfunction "A_A") (pintype "passive"))
      (node (ref "K1") (pin "2") (pinfunction "2_2") (pintype "passive"))
      (node (ref "RL3") (pin "2") (pinfunction "2_2") (pintype "passive"))
      (node (ref "T2") (pin "C") (pinfunction "C_C") (pintype "passive"))
    )
    (net (code "55") (name "Net-(D4-PadA)") (class "Default")
      (node (ref "D4") (pin "A") (pinfunction "A_A") (pintype "passive"))
      (node (ref "K4") (pin "2") (pinfunction "2_2") (pintype "passive"))
      (node (ref "RL4") (pin "2") (pinfunction "2_2") (pintype "passive"))
      (node (ref "T4") (pin "C") (pinfunction "C_C") (pintype "passive"))
    )
    (net (code "56") (name "Net-(F1-2)") (class "Default")
      (node (ref "F1") (pin "3") (pinfunction "2_3") (pintype "bidirectional"))
      (node (ref "POWER") (pin "1") (pinfunction "1_1") (pintype "passive"))
    )
    (net (code "57") (name "Net-(JP2-Pad2)") (class "Default")
      (node (ref "JP2") (pin "2") (pinfunction "2_2") (pintype "passive"))
      (node (ref "RL22") (pin "1") (pinfunction "1_1") (pintype "passive"))
    )
    (net (code "58") (name "Net-(JP3-Pad2)") (class "Default")
      (node (ref "JP3") (pin "2") (pinfunction "2_2") (pintype "passive"))
      (node (ref "RL18") (pin "1") (pinfunction "1_1") (pintype "passive"))
    )
    (net (code "59") (name "Net-(JP5-Pad2)") (class "Default")
      (node (ref "JP5") (pin "2") (pinfunction "2_2") (pintype "passive"))
      (node (ref "RL21") (pin "1") (pinfunction "1_1") (pintype "passive"))
    )
    (net (code "60") (name "Net-(L1-PadA)") (class "Default")
      (node (ref "L1") (pin "A") (pinfunction "A_A") (pintype "passive"))
      (node (ref "RL1") (pin "1") (pinfunction "1_1") (pintype "passive"))
    )
    (net (code "61") (name "Net-(L2-PadA)") (class "Default")
      (node (ref "L2") (pin "A") (pinfunction "A_A") (pintype "passive"))
      (node (ref "RL2") (pin "1") (pinfunction "1_1") (pintype "passive"))
    )
    (net (code "62") (name "Net-(L3-PadA)") (class "Default")
      (node (ref "L3") (pin "A") (pinfunction "A_A") (pintype "passive"))
      (node (ref "RL3") (pin "1") (pinfunction "1_1") (pintype "passive"))
    )
    (net (code "63") (name "Net-(L4-PadA)") (class "Default")
      (node (ref "L4") (pin "A") (pinfunction "A_A") (pintype "passive"))
      (node (ref "RL4") (pin "1") (pinfunction "1_1") (pintype "passive"))
    )
    (net (code "64") (name "Net-(LED_POWER-Pad2)") (class "Default")
      (node (ref "LED_POWER") (pin "2") (pinfunction "2_2") (pintype "passive"))
      (node (ref "RL24") (pin "1") (pinfunction "1_1") (pintype "passive"))
    )
    (net (code "65") (name "Net-(R1-Pad1)") (class "Default")
      (node (ref "R1") (pin "1") (pinfunction "1_1") (pintype "passive"))
      (node (ref "U$3") (pin "15") (pinfunction "15_15") (pintype "bidirectional"))
    )
    (net (code "66") (name "Net-(R2-1)") (class "Default")
      (node (ref "CT1") (pin "P$1") (pinfunction "P$1_P$1") (pintype "bidirectional"))
      (node (ref "R2") (pin "P$1") (pinfunction "1_P$1") (pintype "passive"))
    )
    (net (code "67") (name "Net-(R4-1)") (class "Default")
      (node (ref "CT2") (pin "P$1") (pinfunction "P$1_P$1") (pintype "bidirectional"))
      (node (ref "R4") (pin "P$1") (pinfunction "1_P$1") (pintype "passive"))
    )
    (net (code "68") (name "Net-(R6-1)") (class "Default")
      (node (ref "CT3") (pin "P$1") (pinfunction "P$1_P$1") (pintype "bidirectional"))
      (node (ref "R6") (pin "P$1") (pinfunction "1_P$1") (pintype "passive"))
    )
    (net (code "69") (name "Net-(R8-1)") (class "Default")
      (node (ref "CT4") (pin "P$1") (pinfunction "P$1_P$1") (pintype "bidirectional"))
      (node (ref "R8") (pin "P$1") (pinfunction "1_P$1") (pintype "passive"))
    )
    (net (code "70") (name "Net-(R10-1)") (class "Default")
      (node (ref "CT5") (pin "P$1") (pinfunction "P$1_P$1") (pintype "bidirectional"))
      (node (ref "R10") (pin "P$1") (pinfunction "1_P$1") (pintype "passive"))
    )
    (net (code "71") (name "Net-(R12-1)") (class "Default")
      (node (ref "CT6") (pin "P$1") (pinfunction "P$1_P$1") (pintype "bidirectional"))
      (node (ref "R12") (pin "P$1") (pinfunction "1_P$1") (pintype "passive"))
    )
    (net (code "72") (name "Net-(U$6-IN+)") (class "Default")
      (node (ref "U$6") (pin "I+") (pinfunction "IN+_I+") (pintype "bidirectional"))
      (node (ref "U$9") (pin "P$2") (pinfunction "P$2_P$2") (pintype "bidirectional"))
    )
    (net (code "73") (name "Net-(U$6-IN-)") (class "Default")
      (node (ref "U$6") (pin "I-") (pinfunction "IN-_I-") (pintype "bidirectional"))
      (node (ref "U$9") (pin "P$1") (pinfunction "P$1_P$1") (pintype "bidirectional"))
    )
    (net (code "74") (name "unconnected-(K1-PadO)") (class "Default")
      (node (ref "K1") (pin "O") (pinfunction "O_O") (pintype "passive"))
    )
    (net (code "75") (name "unconnected-(K2-PadO)") (class "Default")
      (node (ref "K2") (pin "O") (pinfunction "O_O") (pintype "passive"))
    )
    (net (code "76") (name "unconnected-(K3-PadO)") (class "Default")
      (node (ref "K3") (pin "O") (pinfunction "O_O") (pintype "passive"))
    )
    (net (code "77") (name "unconnected-(K4-PadO)") (class "Default")
      (node (ref "K4") (pin "O") (pinfunction "O_O") (pintype "passive"))
    )
    (net (code "78") (name "unconnected-(POWERB-1-Pad2)") (class "Default")
      (node (ref "POWER") (pin "2") (pinfunction "1_2") (pintype "passive"))
    )
    (net (code "79") (name "unconnected-(U$3-PadRST)") (class "Default")
      (node (ref "U$3") (pin "RST") (pinfunction "RST_RST") (pintype "bidirectional"))
    )
    (net (code "80") (name "unconnected-(U$5-PadVDD)") (class "Default")
      (node (ref "U$5") (pin "VDD") (pinfunction "VDD_VDD") (pintype "bidirectional"))
    )
    (net (code "81") (name "unconnected-(U$7-PadGND)") (class "Default")
      (node (ref "U$7") (pin "GND") (pinfunction "GND_GND") (pintype "power_in"))
    )
    (net (code "82") (name "unconnected-(U$7-PadRAW)") (class "Default")
      (node (ref "U$7") (pin "RAW") (pinfunction "RAW_RAW") (pintype "bidirectional"))
    )
    (net (code "83") (name "unconnected-(U$7-PadRST)") (class "Default")
      (node (ref "U$7") (pin "RST") (pinfunction "RST_RST") (pintype "bidirectional"))
    )
    (net (code "84") (name "unconnected-(U$7-PadRST2)") (class "Default")
      (node (ref "U$7") (pin "RST2") (pinfunction "RST2_RST2") (pintype "bidirectional"))
    )
    (net (code "85") (name "unconnected-(U$7-PadRX)") (class "Default")
      (node (ref "U$7") (pin "RX") (pinfunction "RX_RX") (pintype "bidirectional"))
    )
    (net (code "86") (name "unconnected-(U$7-PadTX)") (class "Default")
      (node (ref "U$7") (pin "TX") (pinfunction "TX_TX") (pintype "bidirectional"))
    )
  )
)
